# H05-7439.net
KiCad netlist of a schematic drawn in EAGLE
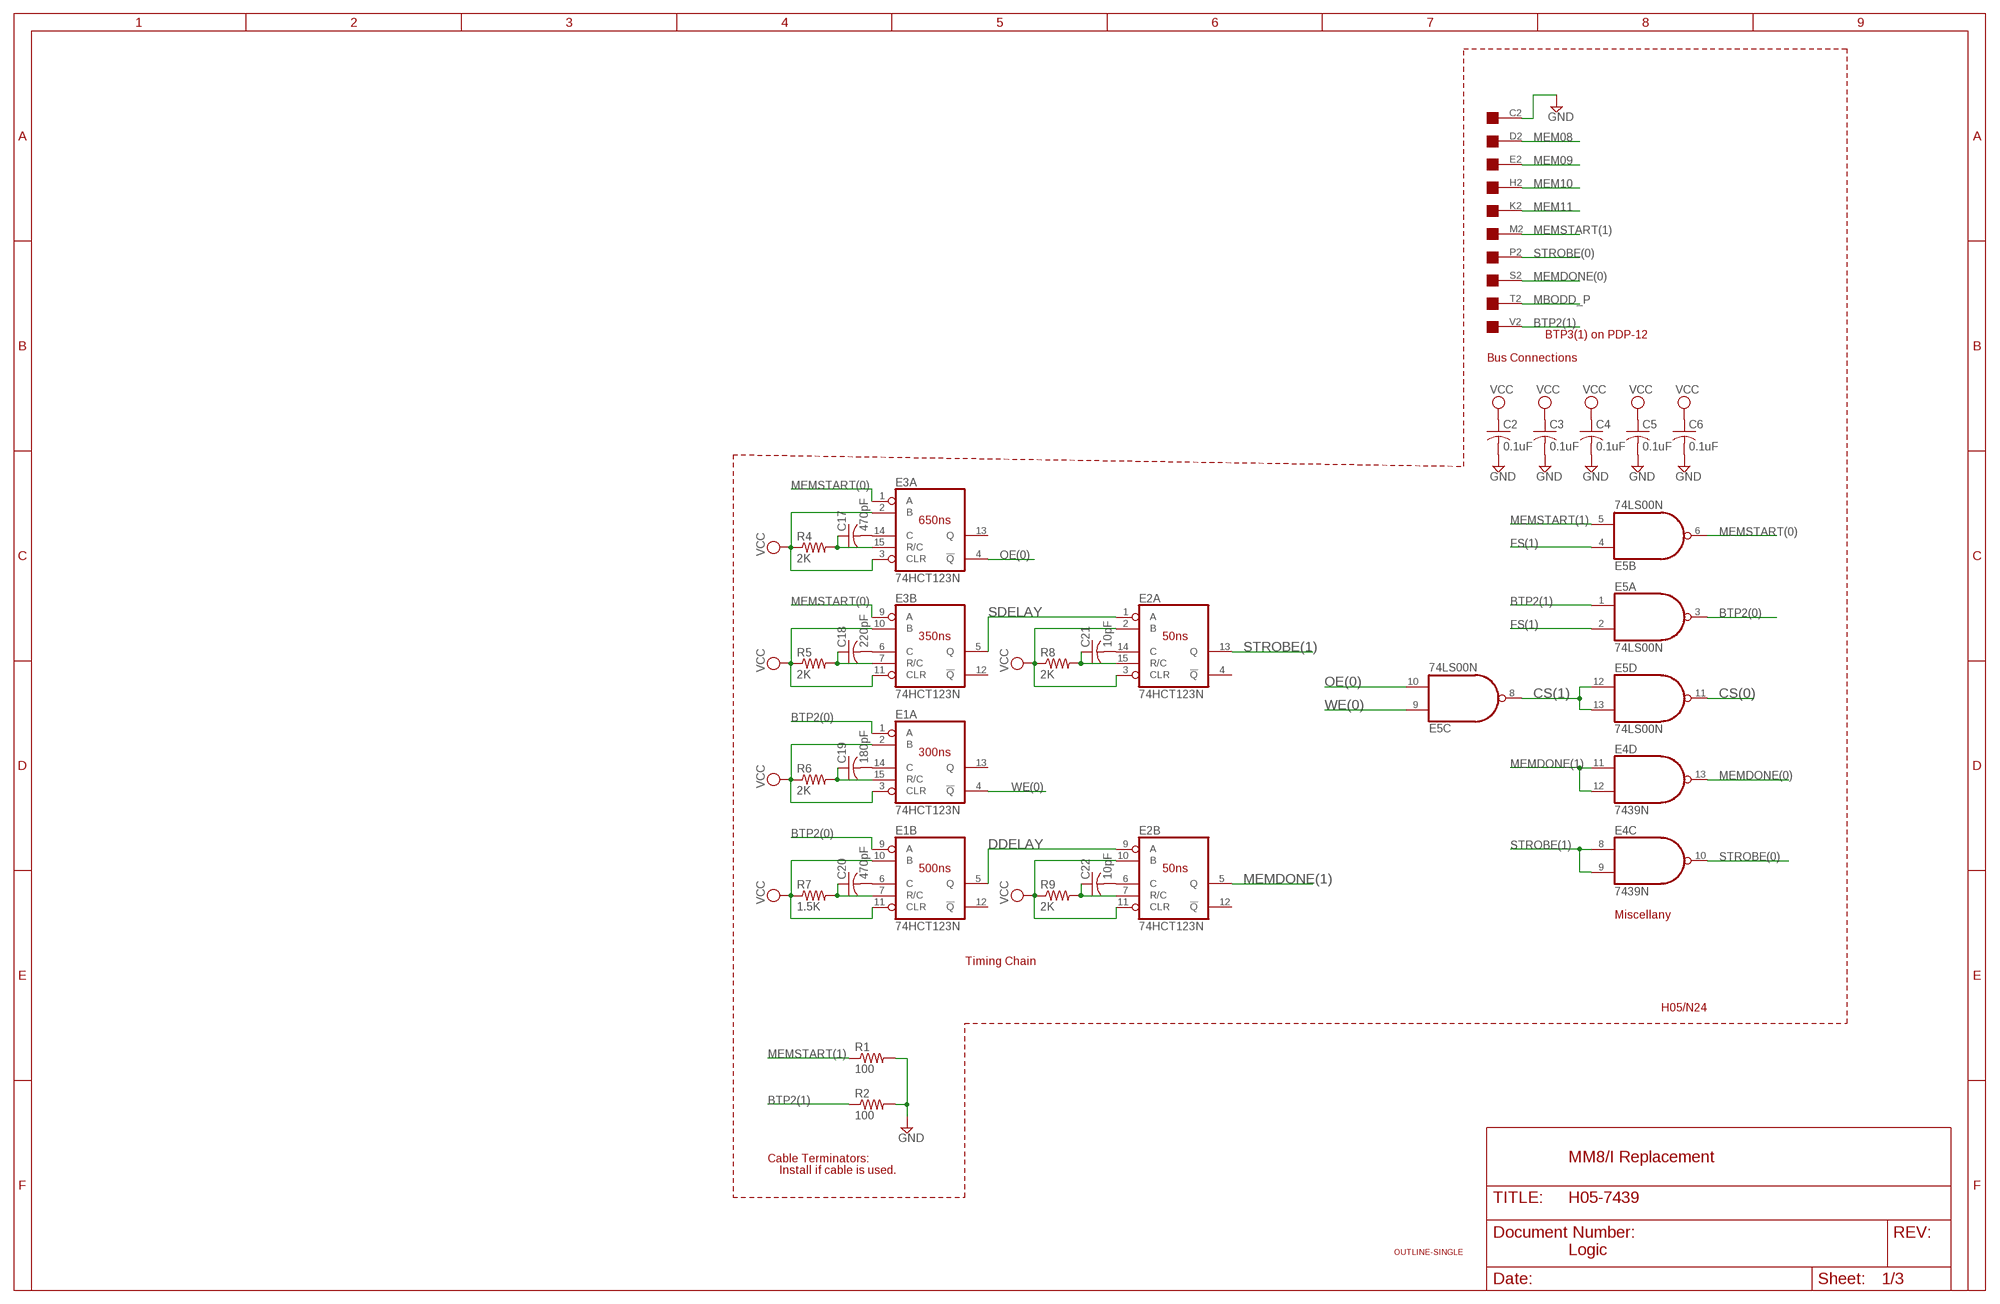
[diagram p0: schematic, sheet 1]
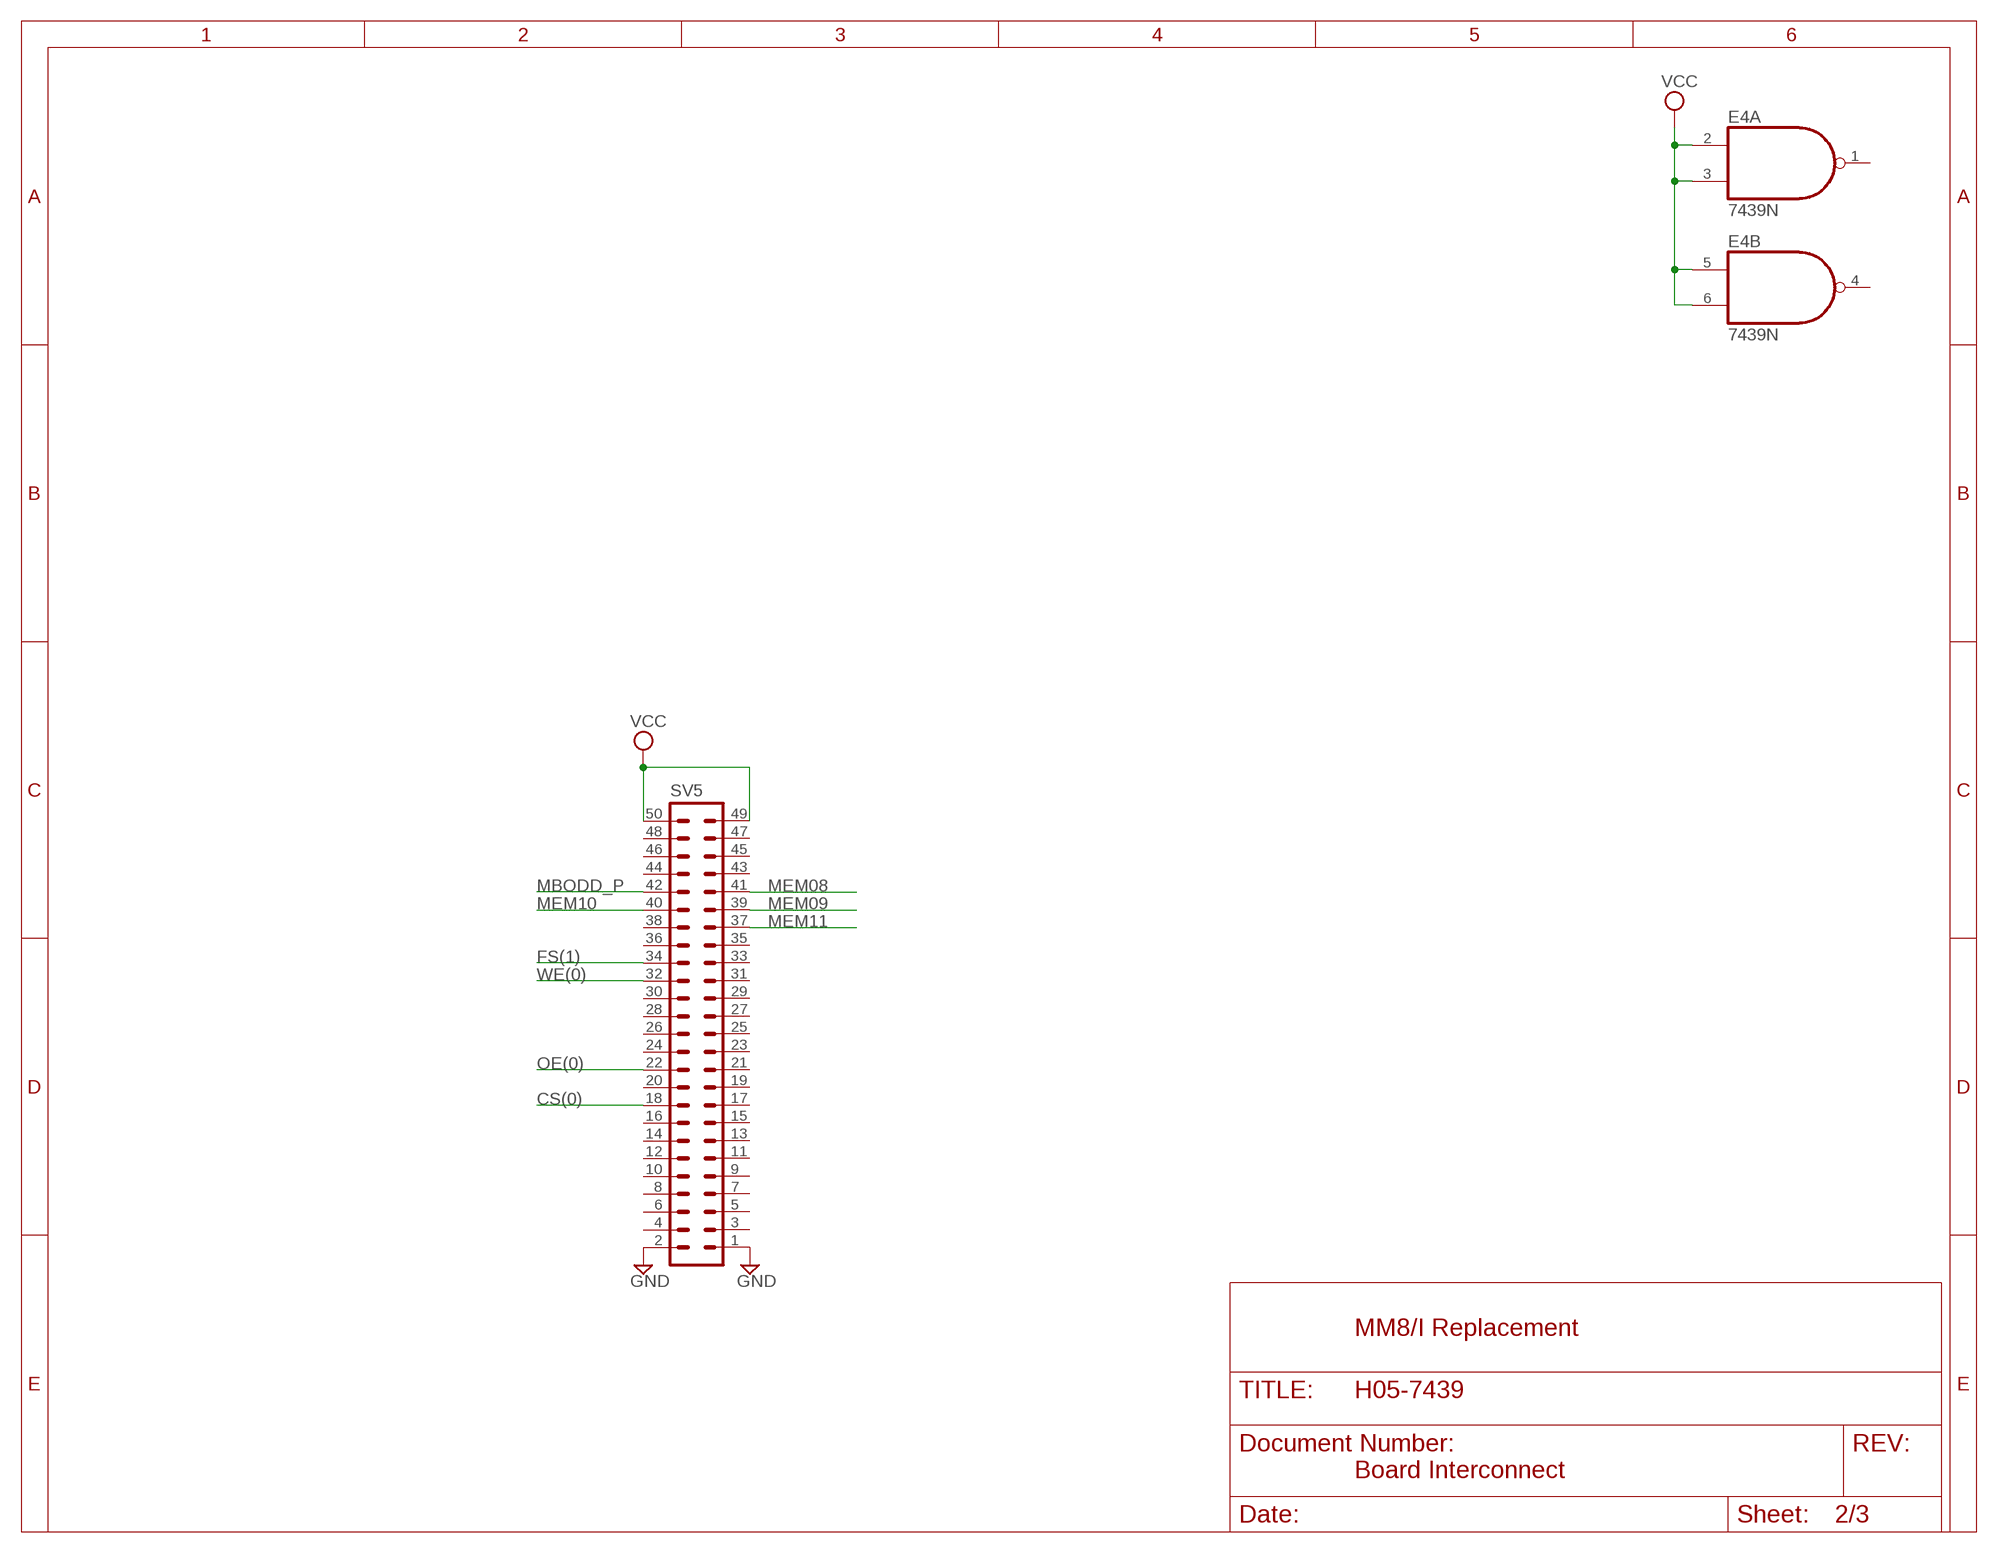
[diagram p1: schematic, sheet 2]
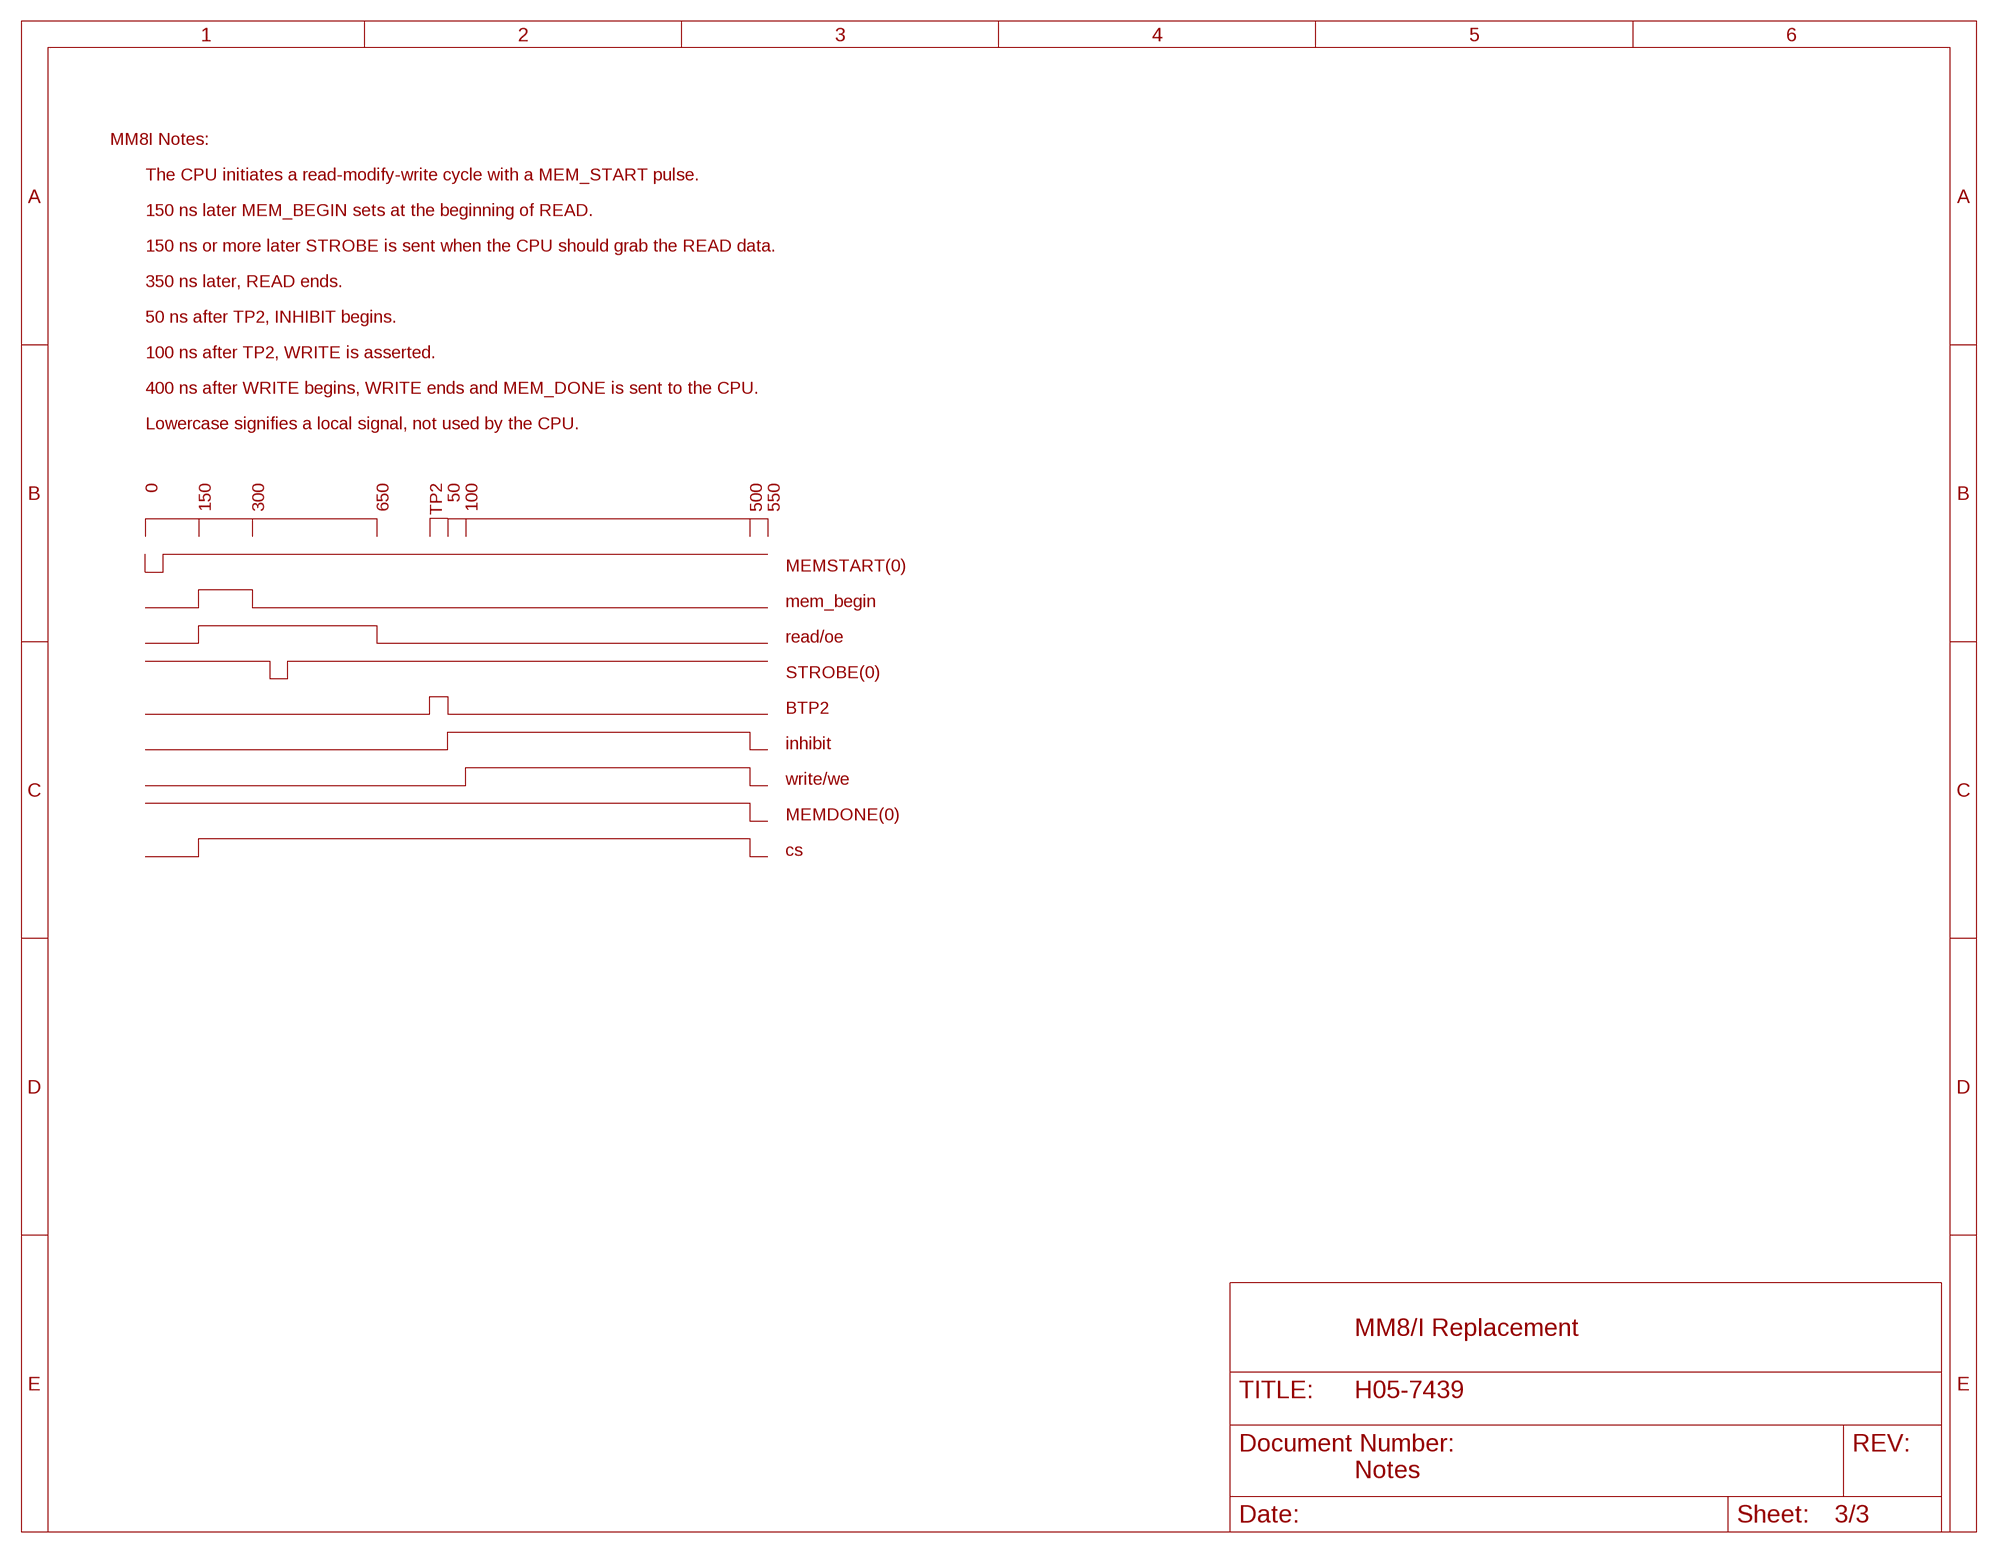
[diagram p2: schematic, sheet 3]

(export (version "E")
  (design (tool "Eeschema 10.0.6"))
  (components
    (comp (ref "E4")
      (value "7439N")
      (footprint "eagle-import:DIL14")
      (libsource (lib "eagle-import") (part "7401NLS"))
    )
    (comp (ref "SV5")
      (value "ML50L")
      (footprint "eagle-import:ML50L")
      (libsource (lib "eagle-import") (part "ML50L"))
    )
    (comp (ref "C2")
      (value "0.1uF")
      (footprint "eagle-import:C050-025X075")
      (libsource (lib "eagle-import") (part "C-US050-025X075"))
    )
    (comp (ref "C3")
      (value "0.1uF")
      (footprint "eagle-import:C050-025X075")
      (libsource (lib "eagle-import") (part "C-US050-025X075"))
    )
    (comp (ref "C4")
      (value "0.1uF")
      (footprint "eagle-import:C050-025X075")
      (libsource (lib "eagle-import") (part "C-US050-025X075"))
    )
    (comp (ref "C5")
      (value "0.1uF")
      (footprint "eagle-import:C050-025X075")
      (libsource (lib "eagle-import") (part "C-US050-025X075"))
    )
    (comp (ref "C6")
      (value "0.1uF")
      (footprint "eagle-import:C050-025X075")
      (libsource (lib "eagle-import") (part "C-US050-025X075"))
    )
    (comp (ref "C17")
      (value "470pF")
      (footprint "eagle-import:C050-025X075")
      (libsource (lib "eagle-import") (part "C-US050-025X075"))
    )
    (comp (ref "C18")
      (value "220pF")
      (footprint "eagle-import:C050-025X075")
      (libsource (lib "eagle-import") (part "C-US050-025X075"))
    )
    (comp (ref "C19")
      (value "180pF")
      (footprint "eagle-import:C050-025X075")
      (libsource (lib "eagle-import") (part "C-US050-025X075"))
    )
    (comp (ref "C20")
      (value "470pF")
      (footprint "eagle-import:C050-025X075")
      (libsource (lib "eagle-import") (part "C-US050-025X075"))
    )
    (comp (ref "C21")
      (value "10pF")
      (footprint "eagle-import:C050-025X075")
      (libsource (lib "eagle-import") (part "C-US050-025X075"))
    )
    (comp (ref "C22")
      (value "10pF")
      (footprint "eagle-import:C050-025X075")
      (libsource (lib "eagle-import") (part "C-US050-025X075"))
    )
    (comp (ref "E1")
      (value "74HCT123N")
      (footprint "eagle-import:DIL16")
      (libsource (lib "eagle-import") (part "74123NLS"))
    )
    (comp (ref "E2")
      (value "74HCT123N")
      (footprint "eagle-import:DIL16")
      (libsource (lib "eagle-import") (part "74123NLS"))
    )
    (comp (ref "E3")
      (value "74HCT123N")
      (footprint "eagle-import:DIL16")
      (libsource (lib "eagle-import") (part "74123NLS"))
    )
    (comp (ref "E5")
      (value "74LS00N")
      (footprint "eagle-import:DIL14")
      (libsource (lib "eagle-import") (part "7400NLS"))
    )
    (comp (ref "H05")
      (value "EDGE-1")
      (footprint "eagle-import:EDGE-CON1")
      (libsource (lib "eagle-import") (part "EDGE-1"))
    )
    (comp (ref "R1")
      (value "100")
      (footprint "eagle-import:0207_10")
      (libsource (lib "eagle-import") (part "R-US_0207/10"))
    )
    (comp (ref "R2")
      (value "100")
      (footprint "eagle-import:0207_10")
      (libsource (lib "eagle-import") (part "R-US_0207/10"))
    )
    (comp (ref "R4")
      (value "2K")
      (footprint "eagle-import:0207_10")
      (libsource (lib "eagle-import") (part "R-US_0207/10"))
    )
    (comp (ref "R5")
      (value "2K")
      (footprint "eagle-import:0207_10")
      (libsource (lib "eagle-import") (part "R-US_0207/10"))
    )
    (comp (ref "R6")
      (value "2K")
      (footprint "eagle-import:0207_10")
      (libsource (lib "eagle-import") (part "R-US_0207/10"))
    )
    (comp (ref "R7")
      (value "1.5K")
      (footprint "eagle-import:0207_10")
      (libsource (lib "eagle-import") (part "R-US_0207/10"))
    )
    (comp (ref "R8")
      (value "2K")
      (footprint "eagle-import:0207_10")
      (libsource (lib "eagle-import") (part "R-US_0207/10"))
    )
    (comp (ref "R9")
      (value "2K")
      (footprint "eagle-import:0207_10")
      (libsource (lib "eagle-import") (part "R-US_0207/10"))
    )
    (comp (ref "U$1")
      (value "OUTLINE-SINGLE")
      (footprint "eagle-import:SINGLE")
      (libsource (lib "eagle-import") (part "OUTLINE-SINGLE"))
    )
  )
  (nets
    (net (code "1") (name "BTP2(0)") (class "Default")
      (node (ref "E1") (pin "1") (pinfunction "A_1") (pintype "input"))
      (node (ref "E1") (pin "9") (pinfunction "A_9") (pintype "input"))
      (node (ref "E5") (pin "3") (pinfunction "O_3") (pintype "output"))
    )
    (net (code "2") (name "BTP2(1)") (class "Default")
      (node (ref "E5") (pin "1") (pinfunction "I0_1") (pintype "input"))
      (node (ref "H05") (pin "V2") (pinfunction "1_V2") (pintype "bidirectional"))
      (node (ref "R2") (pin "1") (pinfunction "1_1") (pintype "passive"))
    )
    (net (code "3") (name "CS(0)") (class "Default")
      (node (ref "E5") (pin "11") (pinfunction "O_11") (pintype "output"))
      (node (ref "SV5") (pin "18") (pinfunction "18_18") (pintype "passive"))
    )
    (net (code "4") (name "CS(1)") (class "Default")
      (node (ref "E5") (pin "12") (pinfunction "I0_12") (pintype "input"))
      (node (ref "E5") (pin "13") (pinfunction "I1_13") (pintype "input"))
      (node (ref "E5") (pin "8") (pinfunction "O_8") (pintype "output"))
    )
    (net (code "5") (name "DDELAY") (class "Default")
      (node (ref "E1") (pin "5") (pinfunction "Q_5") (pintype "output"))
      (node (ref "E2") (pin "9") (pinfunction "A_9") (pintype "input"))
    )
    (net (code "6") (name "FS(1)") (class "Default")
      (node (ref "E5") (pin "2") (pinfunction "I1_2") (pintype "input"))
      (node (ref "E5") (pin "4") (pinfunction "I0_4") (pintype "input"))
      (node (ref "SV5") (pin "34") (pinfunction "34_34") (pintype "passive"))
    )
    (net (code "7") (name "GND") (class "Default")
      (node (ref "C2") (pin "2") (pinfunction "2_2") (pintype "passive"))
      (node (ref "C3") (pin "2") (pinfunction "2_2") (pintype "passive"))
      (node (ref "C4") (pin "2") (pinfunction "2_2") (pintype "passive"))
      (node (ref "C5") (pin "2") (pinfunction "2_2") (pintype "passive"))
      (node (ref "C6") (pin "2") (pinfunction "2_2") (pintype "passive"))
      (node (ref "H05") (pin "C2") (pinfunction "1_C2") (pintype "bidirectional"))
      (node (ref "R1") (pin "2") (pinfunction "2_2") (pintype "passive"))
      (node (ref "R2") (pin "2") (pinfunction "2_2") (pintype "passive"))
      (node (ref "SV5") (pin "1") (pinfunction "1_1") (pintype "passive"))
      (node (ref "SV5") (pin "2") (pinfunction "2_2") (pintype "passive"))
    )
    (net (code "8") (name "MBODD_P") (class "Default")
      (node (ref "H05") (pin "T2") (pinfunction "1_T2") (pintype "bidirectional"))
      (node (ref "SV5") (pin "42") (pinfunction "42_42") (pintype "passive"))
    )
    (net (code "9") (name "MEM08") (class "Default")
      (node (ref "H05") (pin "D2") (pinfunction "1_D2") (pintype "bidirectional"))
      (node (ref "SV5") (pin "41") (pinfunction "41_41") (pintype "passive"))
    )
    (net (code "10") (name "MEM09") (class "Default")
      (node (ref "H05") (pin "E2") (pinfunction "1_E2") (pintype "bidirectional"))
      (node (ref "SV5") (pin "39") (pinfunction "39_39") (pintype "passive"))
    )
    (net (code "11") (name "MEM10") (class "Default")
      (node (ref "H05") (pin "H2") (pinfunction "1_H2") (pintype "bidirectional"))
      (node (ref "SV5") (pin "40") (pinfunction "40_40") (pintype "passive"))
    )
    (net (code "12") (name "MEM11") (class "Default")
      (node (ref "H05") (pin "K2") (pinfunction "1_K2") (pintype "bidirectional"))
      (node (ref "SV5") (pin "37") (pinfunction "37_37") (pintype "passive"))
    )
    (net (code "13") (name "MEMDONE(0)") (class "Default")
      (node (ref "E4") (pin "13") (pinfunction "O_13") (pintype "open_collector"))
      (node (ref "H05") (pin "S2") (pinfunction "1_S2") (pintype "bidirectional"))
    )
    (net (code "14") (name "MEMDONE(1)") (class "Default")
      (node (ref "E2") (pin "5") (pinfunction "Q_5") (pintype "output"))
      (node (ref "E4") (pin "11") (pinfunction "I0_11") (pintype "input"))
      (node (ref "E4") (pin "12") (pinfunction "I1_12") (pintype "input"))
    )
    (net (code "15") (name "MEMSTART(0)") (class "Default")
      (node (ref "E3") (pin "1") (pinfunction "A_1") (pintype "input"))
      (node (ref "E3") (pin "9") (pinfunction "A_9") (pintype "input"))
      (node (ref "E5") (pin "6") (pinfunction "O_6") (pintype "output"))
    )
    (net (code "16") (name "MEMSTART(1)") (class "Default")
      (node (ref "E5") (pin "5") (pinfunction "I1_5") (pintype "input"))
      (node (ref "H05") (pin "M2") (pinfunction "1_M2") (pintype "bidirectional"))
      (node (ref "R1") (pin "1") (pinfunction "1_1") (pintype "passive"))
    )
    (net (code "17") (name "Net-(E1A-C)") (class "Default")
      (node (ref "C19") (pin "2") (pinfunction "2_2") (pintype "passive"))
      (node (ref "E1") (pin "14") (pinfunction "C_14") (pintype "input"))
    )
    (net (code "18") (name "Net-(E1A-R{slash}C)") (class "Default")
      (node (ref "C19") (pin "1") (pinfunction "1_1") (pintype "passive"))
      (node (ref "E1") (pin "15") (pinfunction "R/C_15") (pintype "input"))
      (node (ref "R6") (pin "2") (pinfunction "2_2") (pintype "passive"))
    )
    (net (code "19") (name "Net-(E1B-C)") (class "Default")
      (node (ref "C20") (pin "2") (pinfunction "2_2") (pintype "passive"))
      (node (ref "E1") (pin "6") (pinfunction "C_6") (pintype "input"))
    )
    (net (code "20") (name "Net-(E1B-R{slash}C)") (class "Default")
      (node (ref "C20") (pin "1") (pinfunction "1_1") (pintype "passive"))
      (node (ref "E1") (pin "7") (pinfunction "R/C_7") (pintype "input"))
      (node (ref "R7") (pin "2") (pinfunction "2_2") (pintype "passive"))
    )
    (net (code "21") (name "Net-(E2A-C)") (class "Default")
      (node (ref "C21") (pin "2") (pinfunction "2_2") (pintype "passive"))
      (node (ref "E2") (pin "14") (pinfunction "C_14") (pintype "input"))
    )
    (net (code "22") (name "Net-(E2A-R{slash}C)") (class "Default")
      (node (ref "C21") (pin "1") (pinfunction "1_1") (pintype "passive"))
      (node (ref "E2") (pin "15") (pinfunction "R/C_15") (pintype "input"))
      (node (ref "R8") (pin "2") (pinfunction "2_2") (pintype "passive"))
    )
    (net (code "23") (name "Net-(E2B-C)") (class "Default")
      (node (ref "C22") (pin "2") (pinfunction "2_2") (pintype "passive"))
      (node (ref "E2") (pin "6") (pinfunction "C_6") (pintype "input"))
    )
    (net (code "24") (name "Net-(E2B-R{slash}C)") (class "Default")
      (node (ref "C22") (pin "1") (pinfunction "1_1") (pintype "passive"))
      (node (ref "E2") (pin "7") (pinfunction "R/C_7") (pintype "input"))
      (node (ref "R9") (pin "2") (pinfunction "2_2") (pintype "passive"))
    )
    (net (code "25") (name "Net-(E3A-C)") (class "Default")
      (node (ref "C17") (pin "2") (pinfunction "2_2") (pintype "passive"))
      (node (ref "E3") (pin "14") (pinfunction "C_14") (pintype "input"))
    )
    (net (code "26") (name "Net-(E3A-R{slash}C)") (class "Default")
      (node (ref "C17") (pin "1") (pinfunction "1_1") (pintype "passive"))
      (node (ref "E3") (pin "15") (pinfunction "R/C_15") (pintype "input"))
      (node (ref "R4") (pin "2") (pinfunction "2_2") (pintype "passive"))
    )
    (net (code "27") (name "Net-(E3B-C)") (class "Default")
      (node (ref "C18") (pin "2") (pinfunction "2_2") (pintype "passive"))
      (node (ref "E3") (pin "6") (pinfunction "C_6") (pintype "input"))
    )
    (net (code "28") (name "Net-(E3B-R{slash}C)") (class "Default")
      (node (ref "C18") (pin "1") (pinfunction "1_1") (pintype "passive"))
      (node (ref "E3") (pin "7") (pinfunction "R/C_7") (pintype "input"))
      (node (ref "R5") (pin "2") (pinfunction "2_2") (pintype "passive"))
    )
    (net (code "29") (name "OE(0)") (class "Default")
      (node (ref "E3") (pin "4") (pinfunction "~{Q}_4") (pintype "output"))
      (node (ref "E5") (pin "10") (pinfunction "I1_10") (pintype "input"))
      (node (ref "SV5") (pin "22") (pinfunction "22_22") (pintype "passive"))
    )
    (net (code "30") (name "SDELAY") (class "Default")
      (node (ref "E2") (pin "1") (pinfunction "A_1") (pintype "input"))
      (node (ref "E3") (pin "5") (pinfunction "Q_5") (pintype "output"))
    )
    (net (code "31") (name "STROBE(0)") (class "Default")
      (node (ref "E4") (pin "10") (pinfunction "O_10") (pintype "open_collector"))
      (node (ref "H05") (pin "P2") (pinfunction "1_P2") (pintype "bidirectional"))
    )
    (net (code "32") (name "STROBE(1)") (class "Default")
      (node (ref "E2") (pin "13") (pinfunction "Q_13") (pintype "output"))
      (node (ref "E4") (pin "8") (pinfunction "I0_8") (pintype "input"))
      (node (ref "E4") (pin "9") (pinfunction "I1_9") (pintype "input"))
    )
    (net (code "33") (name "VCC") (class "Default")
      (node (ref "C2") (pin "1") (pinfunction "1_1") (pintype "passive"))
      (node (ref "C3") (pin "1") (pinfunction "1_1") (pintype "passive"))
      (node (ref "C4") (pin "1") (pinfunction "1_1") (pintype "passive"))
      (node (ref "C5") (pin "1") (pinfunction "1_1") (pintype "passive"))
      (node (ref "C6") (pin "1") (pinfunction "1_1") (pintype "passive"))
      (node (ref "E1") (pin "10") (pinfunction "B_10") (pintype "input"))
      (node (ref "E1") (pin "11") (pinfunction "CLR_11") (pintype "input"))
      (node (ref "E1") (pin "2") (pinfunction "B_2") (pintype "input"))
      (node (ref "E1") (pin "3") (pinfunction "CLR_3") (pintype "input"))
      (node (ref "E2") (pin "10") (pinfunction "B_10") (pintype "input"))
      (node (ref "E2") (pin "11") (pinfunction "CLR_11") (pintype "input"))
      (node (ref "E2") (pin "2") (pinfunction "B_2") (pintype "input"))
      (node (ref "E2") (pin "3") (pinfunction "CLR_3") (pintype "input"))
      (node (ref "E3") (pin "10") (pinfunction "B_10") (pintype "input"))
      (node (ref "E3") (pin "11") (pinfunction "CLR_11") (pintype "input"))
      (node (ref "E3") (pin "2") (pinfunction "B_2") (pintype "input"))
      (node (ref "E3") (pin "3") (pinfunction "CLR_3") (pintype "input"))
      (node (ref "E4") (pin "2") (pinfunction "I0_2") (pintype "input"))
      (node (ref "E4") (pin "3") (pinfunction "I1_3") (pintype "input"))
      (node (ref "E4") (pin "5") (pinfunction "I0_5") (pintype "input"))
      (node (ref "E4") (pin "6") (pinfunction "I1_6") (pintype "input"))
      (node (ref "R4") (pin "1") (pinfunction "1_1") (pintype "passive"))
      (node (ref "R5") (pin "1") (pinfunction "1_1") (pintype "passive"))
      (node (ref "R6") (pin "1") (pinfunction "1_1") (pintype "passive"))
      (node (ref "R7") (pin "1") (pinfunction "1_1") (pintype "passive"))
      (node (ref "R8") (pin "1") (pinfunction "1_1") (pintype "passive"))
      (node (ref "R9") (pin "1") (pinfunction "1_1") (pintype "passive"))
      (node (ref "SV5") (pin "49") (pinfunction "49_49") (pintype "passive"))
      (node (ref "SV5") (pin "50") (pinfunction "50_50") (pintype "passive"))
    )
    (net (code "34") (name "WE(0)") (class "Default")
      (node (ref "E1") (pin "4") (pinfunction "~{Q}_4") (pintype "output"))
      (node (ref "E5") (pin "9") (pinfunction "I0_9") (pintype "input"))
      (node (ref "SV5") (pin "32") (pinfunction "32_32") (pintype "passive"))
    )
    (net (code "35") (name "unconnected-(E1A-Q-Pad13)") (class "Default")
      (node (ref "E1") (pin "13") (pinfunction "Q_13") (pintype "output"))
    )
    (net (code "36") (name "unconnected-(E1B-~{Q}-Pad12)") (class "Default")
      (node (ref "E1") (pin "12") (pinfunction "~{Q}_12") (pintype "output"))
    )
    (net (code "37") (name "unconnected-(E2A-~{Q}-Pad4)") (class "Default")
      (node (ref "E2") (pin "4") (pinfunction "~{Q}_4") (pintype "output"))
    )
    (net (code "38") (name "unconnected-(E2B-~{Q}-Pad12)") (class "Default")
      (node (ref "E2") (pin "12") (pinfunction "~{Q}_12") (pintype "output"))
    )
    (net (code "39") (name "unconnected-(E3A-Q-Pad13)") (class "Default")
      (node (ref "E3") (pin "13") (pinfunction "Q_13") (pintype "output"))
    )
    (net (code "40") (name "unconnected-(E3B-~{Q}-Pad12)") (class "Default")
      (node (ref "E3") (pin "12") (pinfunction "~{Q}_12") (pintype "output"))
    )
    (net (code "41") (name "unconnected-(E4A-O-Pad1)") (class "Default")
      (node (ref "E4") (pin "1") (pinfunction "O_1") (pintype "open_collector"))
    )
    (net (code "42") (name "unconnected-(E4B-O-Pad4)") (class "Default")
      (node (ref "E4") (pin "4") (pinfunction "O_4") (pintype "open_collector"))
    )
    (net (code "43") (name "unconnected-(SV5-Pad3)") (class "Default")
      (node (ref "SV5") (pin "3") (pinfunction "3_3") (pintype "passive"))
    )
    (net (code "44") (name "unconnected-(SV5-Pad4)") (class "Default")
      (node (ref "SV5") (pin "4") (pinfunction "4_4") (pintype "passive"))
    )
    (net (code "45") (name "unconnected-(SV5-Pad5)") (class "Default")
      (node (ref "SV5") (pin "5") (pinfunction "5_5") (pintype "passive"))
    )
    (net (code "46") (name "unconnected-(SV5-Pad6)") (class "Default")
      (node (ref "SV5") (pin "6") (pinfunction "6_6") (pintype "passive"))
    )
    (net (code "47") (name "unconnected-(SV5-Pad7)") (class "Default")
      (node (ref "SV5") (pin "7") (pinfunction "7_7") (pintype "passive"))
    )
    (net (code "48") (name "unconnected-(SV5-Pad8)") (class "Default")
      (node (ref "SV5") (pin "8") (pinfunction "8_8") (pintype "passive"))
    )
    (net (code "49") (name "unconnected-(SV5-Pad9)") (class "Default")
      (node (ref "SV5") (pin "9") (pinfunction "9_9") (pintype "passive"))
    )
    (net (code "50") (name "unconnected-(SV5-Pad10)") (class "Default")
      (node (ref "SV5") (pin "10") (pinfunction "10_10") (pintype "passive"))
    )
    (net (code "51") (name "unconnected-(SV5-Pad11)") (class "Default")
      (node (ref "SV5") (pin "11") (pinfunction "11_11") (pintype "passive"))
    )
    (net (code "52") (name "unconnected-(SV5-Pad12)") (class "Default")
      (node (ref "SV5") (pin "12") (pinfunction "12_12") (pintype "passive"))
    )
    (net (code "53") (name "unconnected-(SV5-Pad13)") (class "Default")
      (node (ref "SV5") (pin "13") (pinfunction "13_13") (pintype "passive"))
    )
    (net (code "54") (name "unconnected-(SV5-Pad14)") (class "Default")
      (node (ref "SV5") (pin "14") (pinfunction "14_14") (pintype "passive"))
    )
    (net (code "55") (name "unconnected-(SV5-Pad15)") (class "Default")
      (node (ref "SV5") (pin "15") (pinfunction "15_15") (pintype "passive"))
    )
    (net (code "56") (name "unconnected-(SV5-Pad16)") (class "Default")
      (node (ref "SV5") (pin "16") (pinfunction "16_16") (pintype "passive"))
    )
    (net (code "57") (name "unconnected-(SV5-Pad17)") (class "Default")
      (node (ref "SV5") (pin "17") (pinfunction "17_17") (pintype "passive"))
    )
    (net (code "58") (name "unconnected-(SV5-Pad19)") (class "Default")
      (node (ref "SV5") (pin "19") (pinfunction "19_19") (pintype "passive"))
    )
    (net (code "59") (name "unconnected-(SV5-Pad20)") (class "Default")
      (node (ref "SV5") (pin "20") (pinfunction "20_20") (pintype "passive"))
    )
    (net (code "60") (name "unconnected-(SV5-Pad21)") (class "Default")
      (node (ref "SV5") (pin "21") (pinfunction "21_21") (pintype "passive"))
    )
    (net (code "61") (name "unconnected-(SV5-Pad23)") (class "Default")
      (node (ref "SV5") (pin "23") (pinfunction "23_23") (pintype "passive"))
    )
    (net (code "62") (name "unconnected-(SV5-Pad24)") (class "Default")
      (node (ref "SV5") (pin "24") (pinfunction "24_24") (pintype "passive"))
    )
    (net (code "63") (name "unconnected-(SV5-Pad25)") (class "Default")
      (node (ref "SV5") (pin "25") (pinfunction "25_25") (pintype "passive"))
    )
    (net (code "64") (name "unconnected-(SV5-Pad26)") (class "Default")
      (node (ref "SV5") (pin "26") (pinfunction "26_26") (pintype "passive"))
    )
    (net (code "65") (name "unconnected-(SV5-Pad27)") (class "Default")
      (node (ref "SV5") (pin "27") (pinfunction "27_27") (pintype "passive"))
    )
    (net (code "66") (name "unconnected-(SV5-Pad28)") (class "Default")
      (node (ref "SV5") (pin "28") (pinfunction "28_28") (pintype "passive"))
    )
    (net (code "67") (name "unconnected-(SV5-Pad29)") (class "Default")
      (node (ref "SV5") (pin "29") (pinfunction "29_29") (pintype "passive"))
    )
    (net (code "68") (name "unconnected-(SV5-Pad30)") (class "Default")
      (node (ref "SV5") (pin "30") (pinfunction "30_30") (pintype "passive"))
    )
    (net (code "69") (name "unconnected-(SV5-Pad31)") (class "Default")
      (node (ref "SV5") (pin "31") (pinfunction "31_31") (pintype "passive"))
    )
    (net (code "70") (name "unconnected-(SV5-Pad33)") (class "Default")
      (node (ref "SV5") (pin "33") (pinfunction "33_33") (pintype "passive"))
    )
    (net (code "71") (name "unconnected-(SV5-Pad35)") (class "Default")
      (node (ref "SV5") (pin "35") (pinfunction "35_35") (pintype "passive"))
    )
    (net (code "72") (name "unconnected-(SV5-Pad36)") (class "Default")
      (node (ref "SV5") (pin "36") (pinfunction "36_36") (pintype "passive"))
    )
    (net (code "73") (name "unconnected-(SV5-Pad38)") (class "Default")
      (node (ref "SV5") (pin "38") (pinfunction "38_38") (pintype "passive"))
    )
    (net (code "74") (name "unconnected-(SV5-Pad43)") (class "Default")
      (node (ref "SV5") (pin "43") (pinfunction "43_43") (pintype "passive"))
    )
    (net (code "75") (name "unconnected-(SV5-Pad44)") (class "Default")
      (node (ref "SV5") (pin "44") (pinfunction "44_44") (pintype "passive"))
    )
    (net (code "76") (name "unconnected-(SV5-Pad45)") (class "Default")
      (node (ref "SV5") (pin "45") (pinfunction "45_45") (pintype "passive"))
    )
    (net (code "77") (name "unconnected-(SV5-Pad46)") (class "Default")
      (node (ref "SV5") (pin "46") (pinfunction "46_46") (pintype "passive"))
    )
    (net (code "78") (name "unconnected-(SV5-Pad47)") (class "Default")
      (node (ref "SV5") (pin "47") (pinfunction "47_47") (pintype "passive"))
    )
    (net (code "79") (name "unconnected-(SV5-Pad48)") (class "Default")
      (node (ref "SV5") (pin "48") (pinfunction "48_48") (pintype "passive"))
    )
  )
)
